# Alimentacion_3.net
KiCad netlist of a schematic drawn in Altium Designer
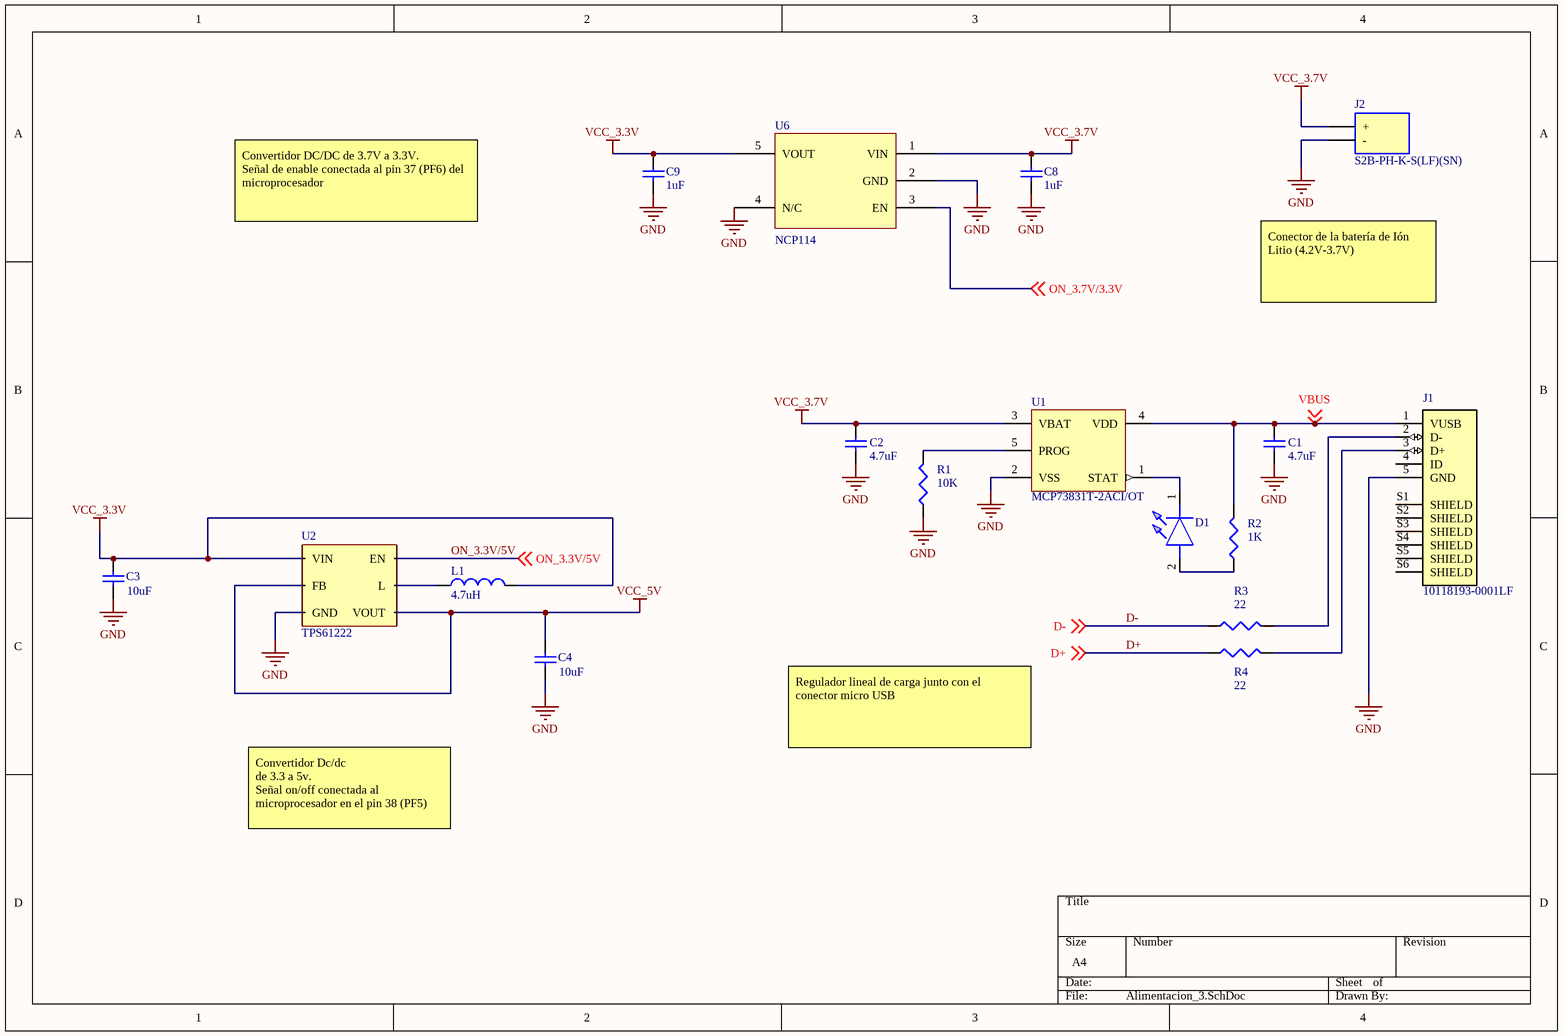
[diagram p0: Alimentacion_3.SchDoc]

(export (version "E")
  (design (tool "Eeschema 10.0.6"))
  (components
    (comp (ref "C1")
      (value "4.7uF")
      (footprint "0603")
      (description "Capacitor")
      (fields (field (name "Comment") "Cap") (field (name "PUBLISHER") "Altium Limited"))
      (libsource (lib "Bicimaps") (part "Cap_0603"))
    )
    (comp (ref "C2")
      (value "4.7uF")
      (footprint "0603")
      (description "Capacitor")
      (fields (field (name "Comment") "Cap") (field (name "PUBLISHER") "Altium Limited"))
      (libsource (lib "Bicimaps") (part "Cap_0603"))
    )
    (comp (ref "C3")
      (value "10uF")
      (footprint "0603")
      (description "Capacitor")
      (fields (field (name "Comment") "Cap") (field (name "PUBLISHER") "Altium Limited"))
      (libsource (lib "Bicimaps") (part "Cap_0603"))
    )
    (comp (ref "C4")
      (value "10uF")
      (footprint "0603")
      (description "Capacitor")
      (fields (field (name "Comment") "Cap") (field (name "PUBLISHER") "Altium Limited"))
      (libsource (lib "Bicimaps") (part "Cap_0603"))
    )
    (comp (ref "C8")
      (value "1uF")
      (footprint "0603")
      (description "Capacitor")
      (fields (field (name "Comment") "Cap") (field (name "PUBLISHER") "Altium Limited"))
      (libsource (lib "Bicimaps") (part "Cap_0603"))
    )
    (comp (ref "C9")
      (value "1uF")
      (footprint "0603")
      (description "Capacitor")
      (fields (field (name "Comment") "Cap") (field (name "PUBLISHER") "Altium Limited"))
      (libsource (lib "Bicimaps") (part "Cap_0603"))
    )
    (comp (ref "D1")
      (value "150060GS75000")
      (footprint "LEDC1608X80N")
      (description "Wurth Elektronik WL-SMCW 520 nm Green LED, 1608 (0603) Clear SMD package")
      (fields (field (name "RS PART NUMBER") "8154209P"))
      (libsource (lib "Bicimaps") (part "150060GS75000"))
    )
    (comp (ref "J1")
      (value "10118193-0001LF")
      (footprint "FCI_10118193-0001LF_10118193-0001LF(Primary)")
      (description "Single Port 5 Contact Shielded SMT MICRO USB B-Type Receptacle")
      (fields (field (name "MF") "Amphenol FCI"))
      (libsource (lib "Bicimaps") (part "10118193-0001LF"))
    )
    (comp (ref "J2")
      (value "S2B-PH-K-S(LF)(SN)")
      (footprint "S2B_Lipo_Header")
      (fields (field (name "RS PART NUMBER") "1724889"))
      (libsource (lib "Bicimaps") (part "S2B-PH-K-S(LF)(SN)"))
    )
    (comp (ref "L1")
      (value "4.7uH")
      (footprint "0603")
      (description "Inductor")
      (fields (field (name "PUBLISHER") "Altium Limited"))
      (libsource (lib "Bicimaps") (part "Inductor"))
    )
    (comp (ref "R1")
      (value "10K")
      (footprint "0603")
      (description "Resistor")
      (fields (field (name "Comment") "Res3") (field (name "PUBLISHER") "Altium Limited"))
      (libsource (lib "Miscellaneous Devices") (part "Res3"))
    )
    (comp (ref "R2")
      (value "1K")
      (footprint "0603")
      (description "Resistor")
      (fields (field (name "Comment") "Res3") (field (name "PUBLISHER") "Altium Limited"))
      (libsource (lib "Miscellaneous Devices") (part "Res3"))
    )
    (comp (ref "R3")
      (value "22")
      (footprint "0603")
      (description "Resistor")
      (fields (field (name "Comment") "Res3") (field (name "PUBLISHER") "Altium Limited"))
      (libsource (lib "Miscellaneous Devices") (part "Res3"))
    )
    (comp (ref "R4")
      (value "22")
      (footprint "0603")
      (description "Resistor")
      (fields (field (name "Comment") "Res3") (field (name "PUBLISHER") "Altium Limited"))
      (libsource (lib "Miscellaneous Devices") (part "Res3"))
    )
    (comp (ref "U1")
      (value "MCP73831T-2ACI/OT")
      (footprint "SOT-23-OT5_N")
      (fields (field (name "PUBLISHER") "Altium Limited"))
      (libsource (lib "Microchip Power Mgt Battery Management") (part "MCP73831T-2ACI/OT"))
    )
    (comp (ref "U2")
      (value "TPS61222")
      (footprint "TPS61222DCK")
      (libsource (lib "Bicimaps") (part "TPS61222"))
    )
    (comp (ref "U6")
      (value "NCP114")
      (footprint "NCP114-TSOP5")
      (libsource (lib "BiciMaps_3") (part "NCP114"))
    )
  )
  (nets
    (net (code "1") (name "D+") (class "Default")
      (node (ref "R4") (pin "1") (pinfunction "1_1") (pintype "passive"))
    )
    (net (code "2") (name "D-") (class "Default")
      (node (ref "R3") (pin "1") (pinfunction "1_1") (pintype "passive"))
    )
    (net (code "3") (name "GND") (class "Default")
      (node (ref "C1") (pin "1") (pinfunction "1_1") (pintype "passive"))
      (node (ref "C2") (pin "1") (pinfunction "1_1") (pintype "passive"))
      (node (ref "C3") (pin "1") (pinfunction "1_1") (pintype "passive"))
      (node (ref "C4") (pin "1") (pinfunction "1_1") (pintype "passive"))
      (node (ref "C8") (pin "1") (pinfunction "1_1") (pintype "passive"))
      (node (ref "C9") (pin "1") (pinfunction "1_1") (pintype "passive"))
      (node (ref "J1") (pin "5") (pinfunction "GND_5") (pintype "power_in"))
      (node (ref "J2") (pin "2") (pinfunction "-_2") (pintype "power_in"))
      (node (ref "R1") (pin "1") (pinfunction "1_1") (pintype "passive"))
      (node (ref "U1") (pin "2") (pinfunction "VSS_2") (pintype "power_in"))
      (node (ref "U2") (pin "GND") (pinfunction "GND_GND") (pintype "power_in"))
      (node (ref "U6") (pin "2") (pinfunction "GND_2") (pintype "passive"))
      (node (ref "U6") (pin "4") (pinfunction "N/C_4") (pintype "passive"))
    )
    (net (code "4") (name "Net-(D1-A)") (class "Default")
      (node (ref "D1") (pin "2") (pinfunction "A_2") (pintype "passive"))
      (node (ref "R2") (pin "1") (pinfunction "1_1") (pintype "passive"))
    )
    (net (code "5") (name "Net-(D1-K)") (class "Default")
      (node (ref "D1") (pin "1") (pinfunction "K_1") (pintype "passive"))
      (node (ref "U1") (pin "1") (pinfunction "STAT_1") (pintype "output"))
    )
    (net (code "6") (name "Net-(J1-D+)") (class "Default")
      (node (ref "J1") (pin "3") (pinfunction "D+_3") (pintype "bidirectional"))
      (node (ref "R4") (pin "2") (pinfunction "2_2") (pintype "passive"))
    )
    (net (code "7") (name "Net-(J1-D-)") (class "Default")
      (node (ref "J1") (pin "2") (pinfunction "D-_2") (pintype "bidirectional"))
      (node (ref "R3") (pin "2") (pinfunction "2_2") (pintype "passive"))
    )
    (net (code "8") (name "Net-(L1-Pad1)") (class "Default")
      (node (ref "L1") (pin "1") (pinfunction "1_1") (pintype "passive"))
      (node (ref "U2") (pin "L") (pinfunction "L_L") (pintype "input"))
    )
    (net (code "9") (name "Net-(U1-PROG)") (class "Default")
      (node (ref "R1") (pin "2") (pinfunction "2_2") (pintype "passive"))
      (node (ref "U1") (pin "5") (pinfunction "PROG_5") (pintype "passive"))
    )
    (net (code "10") (name "ON_3.3V{slash}5V") (class "Default")
      (node (ref "U2") (pin "EN") (pinfunction "EN_EN") (pintype "input"))
    )
    (net (code "11") (name "ON_3.7V{slash}3.3V") (class "Default")
      (node (ref "U6") (pin "3") (pinfunction "EN_3") (pintype "passive"))
    )
    (net (code "12") (name "VBUS") (class "Default")
      (node (ref "C1") (pin "2") (pinfunction "2_2") (pintype "passive"))
      (node (ref "J1") (pin "1") (pinfunction "VUSB_1") (pintype "passive"))
      (node (ref "R2") (pin "2") (pinfunction "2_2") (pintype "passive"))
      (node (ref "U1") (pin "4") (pinfunction "VDD_4") (pintype "power_in"))
    )
    (net (code "13") (name "VCC_3.3V") (class "Default")
      (node (ref "C3") (pin "2") (pinfunction "2_2") (pintype "passive"))
      (node (ref "C9") (pin "2") (pinfunction "2_2") (pintype "passive"))
      (node (ref "L1") (pin "2") (pinfunction "2_2") (pintype "passive"))
      (node (ref "U2") (pin "VIN") (pinfunction "VIN_VIN") (pintype "power_in"))
      (node (ref "U6") (pin "5") (pinfunction "VOUT_5") (pintype "passive"))
    )
    (net (code "14") (name "VCC_3.7V") (class "Default")
      (node (ref "C2") (pin "2") (pinfunction "2_2") (pintype "passive"))
      (node (ref "C8") (pin "2") (pinfunction "2_2") (pintype "passive"))
      (node (ref "J2") (pin "1") (pinfunction "+_1") (pintype "power_in"))
      (node (ref "U1") (pin "3") (pinfunction "VBAT_3") (pintype "power_in"))
      (node (ref "U6") (pin "1") (pinfunction "VIN_1") (pintype "passive"))
    )
    (net (code "15") (name "VCC_5V") (class "Default")
      (node (ref "C4") (pin "2") (pinfunction "2_2") (pintype "passive"))
      (node (ref "U2") (pin "FB") (pinfunction "FB_FB") (pintype "input"))
      (node (ref "U2") (pin "VOUT") (pinfunction "VOUT_VOUT") (pintype "power_in"))
    )
    (net (code "16") (name "unconnected-(J1-ID-Pad4)") (class "Default")
      (node (ref "J1") (pin "4") (pinfunction "ID_4") (pintype "passive"))
    )
    (net (code "17") (name "unconnected-(J1-SHIELD-PadS1)") (class "Default")
      (node (ref "J1") (pin "S1") (pinfunction "SHIELD_S1") (pintype "passive"))
    )
    (net (code "18") (name "unconnected-(J1-SHIELD-PadS2)") (class "Default")
      (node (ref "J1") (pin "S2") (pinfunction "SHIELD_S2") (pintype "passive"))
    )
    (net (code "19") (name "unconnected-(J1-SHIELD-PadS3)") (class "Default")
      (node (ref "J1") (pin "S3") (pinfunction "SHIELD_S3") (pintype "passive"))
    )
    (net (code "20") (name "unconnected-(J1-SHIELD-PadS4)") (class "Default")
      (node (ref "J1") (pin "S4") (pinfunction "SHIELD_S4") (pintype "passive"))
    )
    (net (code "21") (name "unconnected-(J1-SHIELD-PadS5)") (class "Default")
      (node (ref "J1") (pin "S5") (pinfunction "SHIELD_S5") (pintype "passive"))
    )
    (net (code "22") (name "unconnected-(J1-SHIELD-PadS6)") (class "Default")
      (node (ref "J1") (pin "S6") (pinfunction "SHIELD_S6") (pintype "passive"))
    )
  )
)
